# Controller_1.net
KiCad netlist of a schematic drawn in Altium Designer
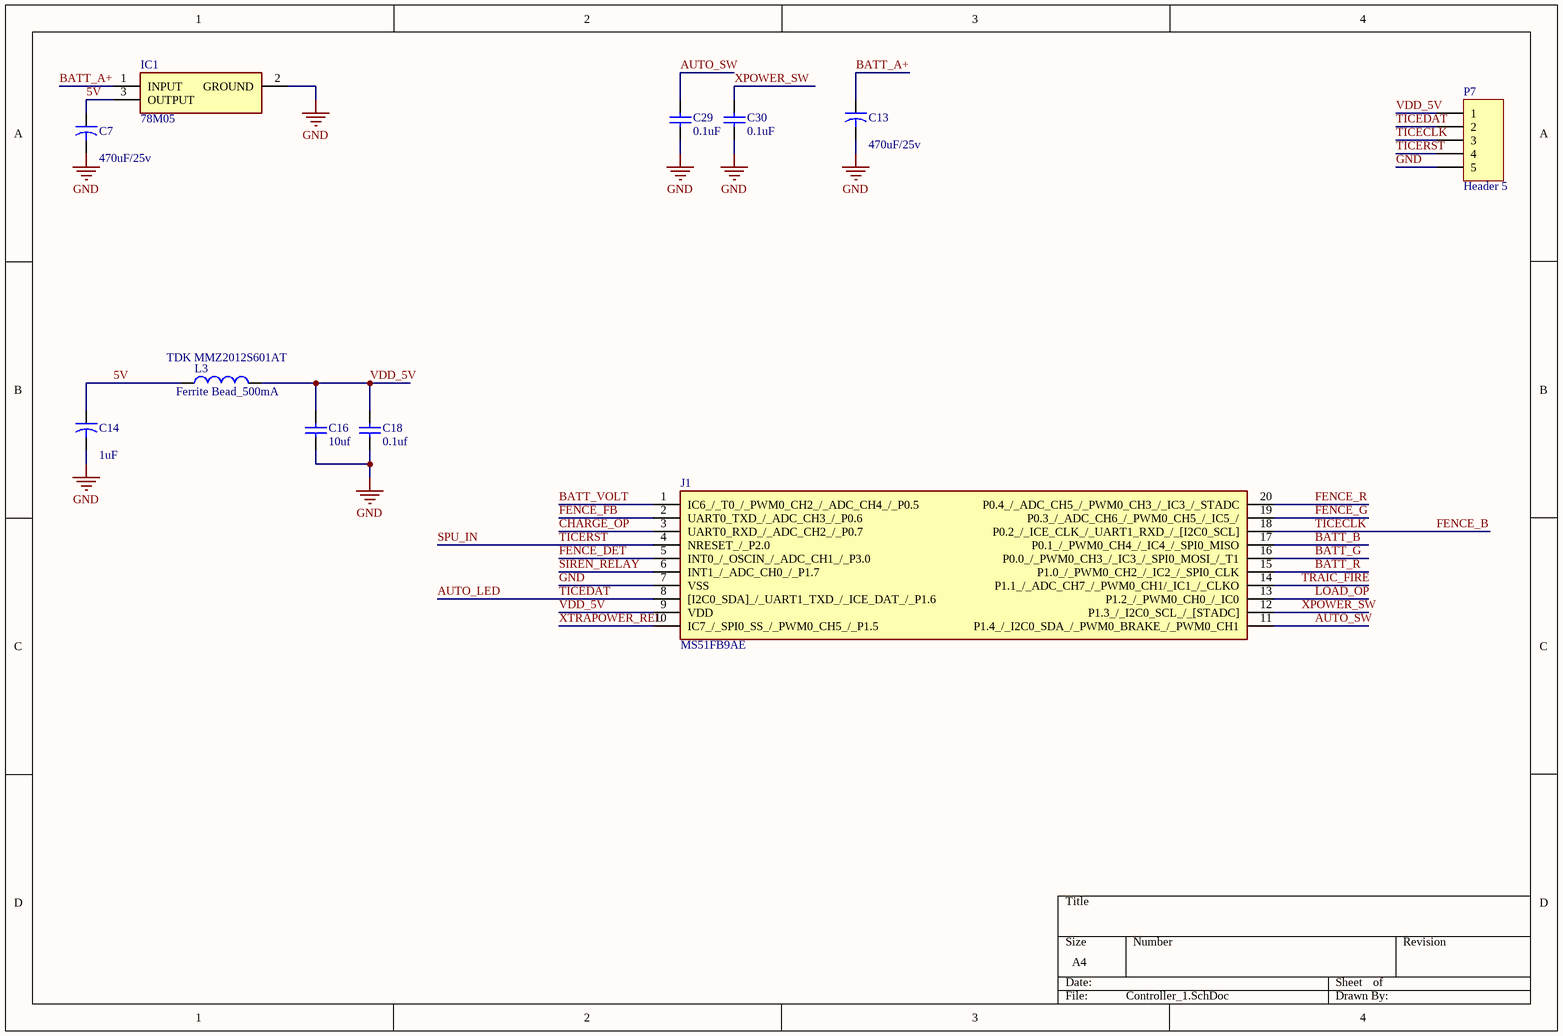
[diagram p0: Controller_1.SchDoc]

(export (version "E")
  (design (tool "Eeschema 10.0.6"))
  (components
    (comp (ref "C7")
      (value "470uF/25v")
      (footprint "Cap_470uf_10X10.2mm")
      (description "Capacitor")
      (fields (field (name "Comment") "Cap2") (field (name "PUBLISHER") "Altium Limited"))
      (libsource (lib "Miscellaneous Devices") (part "Cap2"))
    )
    (comp (ref "C13")
      (value "470uF/25v")
      (footprint "Cap_470uf_10X10.2mm")
      (description "Capacitor")
      (fields (field (name "Comment") "Cap2") (field (name "PUBLISHER") "Altium Limited"))
      (libsource (lib "Miscellaneous Devices") (part "Cap2"))
    )
    (comp (ref "C14")
      (value "1uF")
      (footprint "SMDlibrary:0805")
      (description "Capacitor")
      (fields (field (name "Comment") "Cap2") (field (name "PUBLISHER") "Altium Limited"))
      (libsource (lib "Miscellaneous Devices") (part "Cap2"))
    )
    (comp (ref "C16")
      (value "10uf")
      (footprint "0805")
      (description "Capacitor")
      (fields (field (name "Comment") "Cap") (field (name "PUBLISHER") "Altium Limited"))
      (libsource (lib "Miscellaneous Devices") (part "Cap"))
    )
    (comp (ref "C18")
      (value "0.1uf")
      (footprint "0805")
      (description "Capacitor")
      (fields (field (name "Comment") "Cap") (field (name "PUBLISHER") "Altium Limited"))
      (libsource (lib "Miscellaneous Devices") (part "Cap"))
    )
    (comp (ref "C29")
      (value "0.1uF")
      (footprint "0805")
      (description "Capacitor")
      (fields (field (name "Comment") "Cap") (field (name "PUBLISHER") "Altium Limited"))
      (libsource (lib "Miscellaneous Devices") (part "Cap"))
    )
    (comp (ref "C30")
      (value "0.1uF")
      (footprint "0805")
      (description "Capacitor")
      (fields (field (name "Comment") "Cap") (field (name "PUBLISHER") "Altium Limited"))
      (libsource (lib "Miscellaneous Devices") (part "Cap"))
    )
    (comp (ref "IC1")
      (value "78M05")
      (footprint "SamacSys:TS78M05CP")
      (description "Integrated Circuit")
      (fields
        (field (name "MANUFACTURER_PART_NUMBER") "TS78M05CP")
        (field (name "MOUSER PART NUMBER") "821-TS78M05CP")
      )
      (libsource (lib "*") (part "TS78M05CP"))
    )
    (comp (ref "J1")
      (value "MS51FB9AE")
      (footprint "SamacSys:SOP65P640X120-20N")
      (description "Controller")
      (libsource (lib "*") (part "MS51FB9AE"))
    )
    (comp (ref "L3")
      (value "Ferrite Bead_500mA")
      (footprint "SMDlibrary:0805")
      (description "Inductor")
      (fields (field (name "ALTIUM_VALUE") "TDK MMZ2012S601AT") (field (name "PUBLISHER") "Altium Limited"))
      (libsource (lib "Miscellaneous Devices") (part "Inductor"))
    )
    (comp (ref "P7")
      (value "Header 5")
      (footprint "PCBLIB:HEADER 2.5MM 5PIN")
      (description "Header, 5-Pin")
      (fields (field (name "PUBLISHER") "Altium Limited"))
      (libsource (lib "Miscellaneous Connectors") (part "Header 5"))
    )
  )
  (nets
    (net (code "1") (name "/5V") (class "Default")
      (node (ref "C14") (pin "1") (pinfunction "1_1") (pintype "passive"))
      (node (ref "C7") (pin "1") (pinfunction "1_1") (pintype "passive"))
      (node (ref "IC1") (pin "3") (pinfunction "OUTPUT_3") (pintype "passive"))
      (node (ref "L3") (pin "1") (pinfunction "1_1") (pintype "passive"))
    )
    (net (code "2") (name "/AUTO_LED") (class "Default")
      (node (ref "J1") (pin "8") (pinfunction "[I2C0_SDA]_/_UART1_TXD_/_ICE_DAT_/_P1.6_8") (pintype "passive"))
      (node (ref "P7") (pin "2") (pinfunction "2_2") (pintype "passive"))
    )
    (net (code "3") (name "/AUTO_SW") (class "Default")
      (node (ref "C29") (pin "1") (pinfunction "1_1") (pintype "passive"))
      (node (ref "J1") (pin "11") (pinfunction "P1.4_/_I2C0_SDA_/_PWM0_BRAKE_/_PWM0_CH1_11") (pintype "passive"))
    )
    (net (code "4") (name "/BATT_A+") (class "Default")
      (node (ref "C13") (pin "1") (pinfunction "1_1") (pintype "passive"))
      (node (ref "IC1") (pin "1") (pinfunction "INPUT_1") (pintype "passive"))
    )
    (net (code "5") (name "/BATT_B") (class "Default")
      (node (ref "J1") (pin "17") (pinfunction "P0.1_/_PWM0_CH4_/_IC4_/_SPI0_MISO_17") (pintype "passive"))
    )
    (net (code "6") (name "/BATT_G") (class "Default")
      (node (ref "J1") (pin "16") (pinfunction "P0.0_/_PWM0_CH3_/_IC3_/_SPI0_MOSI_/_T1_16") (pintype "passive"))
    )
    (net (code "7") (name "/BATT_R") (class "Default")
      (node (ref "J1") (pin "15") (pinfunction "P1.0_/_PWM0_CH2_/_IC2_/_SPI0_CLK_15") (pintype "passive"))
    )
    (net (code "8") (name "/BATT_VOLT") (class "Default")
      (node (ref "J1") (pin "1") (pinfunction "IC6_/_T0_/_PWM0_CH2_/_ADC_CH4_/_P0.5_1") (pintype "passive"))
    )
    (net (code "9") (name "/CHARGE_OP") (class "Default")
      (node (ref "J1") (pin "3") (pinfunction "UART0_RXD_/_ADC_CH2_/_P0.7_3") (pintype "passive"))
    )
    (net (code "10") (name "/FENCE_B") (class "Default")
      (node (ref "J1") (pin "18") (pinfunction "P0.2_/_ICE_CLK_/_UART1_RXD_/_[I2C0_SCL]_18") (pintype "passive"))
      (node (ref "P7") (pin "3") (pinfunction "3_3") (pintype "passive"))
    )
    (net (code "11") (name "/FENCE_DET") (class "Default")
      (node (ref "J1") (pin "5") (pinfunction "INT0_/_OSCIN_/_ADC_CH1_/_P3.0_5") (pintype "passive"))
    )
    (net (code "12") (name "/FENCE_FB") (class "Default")
      (node (ref "J1") (pin "2") (pinfunction "UART0_TXD_/_ADC_CH3_/_P0.6_2") (pintype "passive"))
    )
    (net (code "13") (name "/FENCE_G") (class "Default")
      (node (ref "J1") (pin "19") (pinfunction "P0.3_/_ADC_CH6_/_PWM0_CH5_/_IC5_/_19") (pintype "passive"))
    )
    (net (code "14") (name "/FENCE_R") (class "Default")
      (node (ref "J1") (pin "20") (pinfunction "P0.4_/_ADC_CH5_/_PWM0_CH3_/_IC3_/_STADC_20") (pintype "passive"))
    )
    (net (code "15") (name "/LOAD_OP") (class "Default")
      (node (ref "J1") (pin "13") (pinfunction "P1.2_/_PWM0_CH0_/_IC0_13") (pintype "passive"))
    )
    (net (code "16") (name "/SIREN_RELAY") (class "Default")
      (node (ref "J1") (pin "6") (pinfunction "INT1_/_ADC_CH0_/_P1.7_6") (pintype "passive"))
    )
    (net (code "17") (name "/SPU_IN") (class "Default")
      (node (ref "J1") (pin "4") (pinfunction "NRESET_/_P2.0_4") (pintype "passive"))
      (node (ref "P7") (pin "4") (pinfunction "4_4") (pintype "passive"))
    )
    (net (code "18") (name "/TRAIC_FIRE") (class "Default")
      (node (ref "J1") (pin "14") (pinfunction "P1.1_/_ADC_CH7_/_PWM0_CH1/_IC1_/_CLKO_14") (pintype "passive"))
    )
    (net (code "19") (name "/VDD_5V") (class "Default")
      (node (ref "C16") (pin "2") (pinfunction "2_2") (pintype "passive"))
      (node (ref "C18") (pin "2") (pinfunction "2_2") (pintype "passive"))
      (node (ref "J1") (pin "9") (pinfunction "VDD_9") (pintype "passive"))
      (node (ref "L3") (pin "2") (pinfunction "2_2") (pintype "passive"))
      (node (ref "P7") (pin "1") (pinfunction "1_1") (pintype "passive"))
    )
    (net (code "20") (name "/XPOWER_SW") (class "Default")
      (node (ref "C30") (pin "1") (pinfunction "1_1") (pintype "passive"))
      (node (ref "J1") (pin "12") (pinfunction "P1.3_/_I2C0_SCL_/_[STADC]_12") (pintype "passive"))
    )
    (net (code "21") (name "/XTRAPOWER_REL") (class "Default")
      (node (ref "J1") (pin "10") (pinfunction "IC7_/_SPI0_SS_/_PWM0_CH5_/_P1.5_10") (pintype "passive"))
    )
    (net (code "22") (name "GND") (class "Default")
      (node (ref "C13") (pin "2") (pinfunction "2_2") (pintype "passive"))
      (node (ref "C14") (pin "2") (pinfunction "2_2") (pintype "passive"))
      (node (ref "C16") (pin "1") (pinfunction "1_1") (pintype "passive"))
      (node (ref "C18") (pin "1") (pinfunction "1_1") (pintype "passive"))
      (node (ref "C29") (pin "2") (pinfunction "2_2") (pintype "passive"))
      (node (ref "C30") (pin "2") (pinfunction "2_2") (pintype "passive"))
      (node (ref "C7") (pin "2") (pinfunction "2_2") (pintype "passive"))
      (node (ref "IC1") (pin "2") (pinfunction "GROUND_2") (pintype "passive"))
      (node (ref "J1") (pin "7") (pinfunction "VSS_7") (pintype "passive"))
      (node (ref "P7") (pin "5") (pinfunction "5_5") (pintype "passive"))
    )
  )
)
